# base-6u-generic-xau4.net
KiCad netlist of a schematic drawn in EAGLE
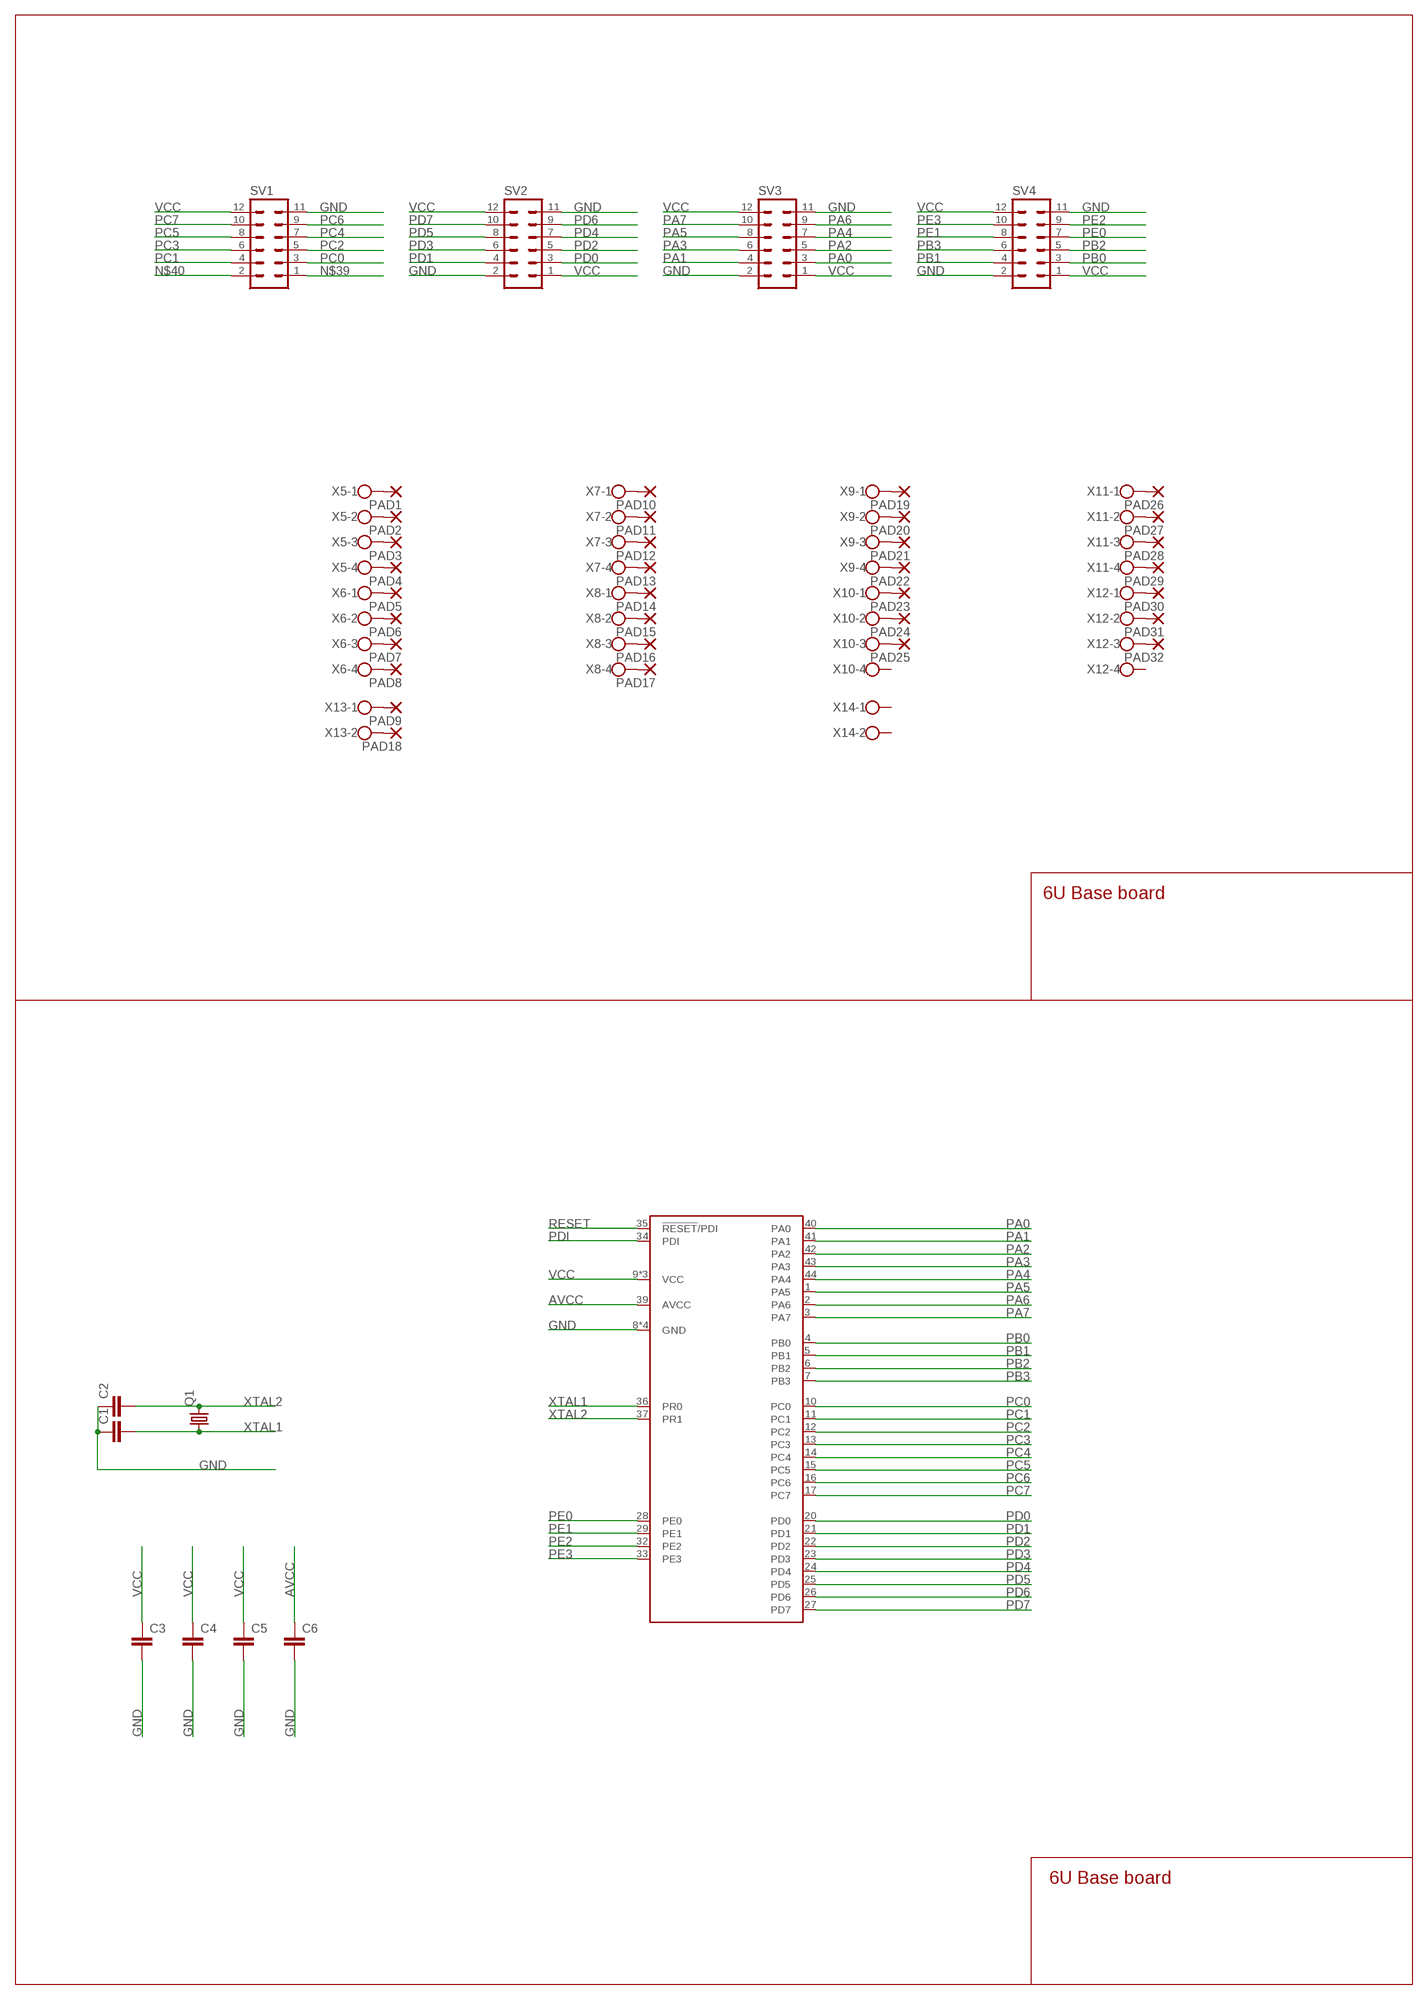
[diagram p0: schematic, sheet 1]

(export (version "E")
  (design (tool "Eeschema 10.0.6"))
  (components
    (comp (ref "C1")
      (value "C-EUC0805")
      (footprint "eagle-import:C0805")
      (libsource (lib "eagle-import") (part "C-EUC0805"))
    )
    (comp (ref "C2")
      (value "C-EUC0805")
      (footprint "eagle-import:C0805")
      (libsource (lib "eagle-import") (part "C-EUC0805"))
    )
    (comp (ref "C3")
      (value "C-EUC0603")
      (footprint "eagle-import:C0603")
      (libsource (lib "eagle-import") (part "C-EUC0603"))
    )
    (comp (ref "C4")
      (value "C-EUC0603")
      (footprint "eagle-import:C0603")
      (libsource (lib "eagle-import") (part "C-EUC0603"))
    )
    (comp (ref "C5")
      (value "C-EUC0603")
      (footprint "eagle-import:C0603")
      (libsource (lib "eagle-import") (part "C-EUC0603"))
    )
    (comp (ref "C6")
      (value "C-EUC0603")
      (footprint "eagle-import:C0603")
      (libsource (lib "eagle-import") (part "C-EUC0603"))
    )
    (comp (ref "PAD1")
      (value "2,54/0,8")
      (footprint "eagle-import:2,54_0,8")
      (libsource (lib "eagle-import") (part "2,54/0,8"))
    )
    (comp (ref "PAD2")
      (value "2,54/0,8")
      (footprint "eagle-import:2,54_0,8")
      (libsource (lib "eagle-import") (part "2,54/0,8"))
    )
    (comp (ref "PAD3")
      (value "2,54/0,8")
      (footprint "eagle-import:2,54_0,8")
      (libsource (lib "eagle-import") (part "2,54/0,8"))
    )
    (comp (ref "PAD4")
      (value "2,54/0,8")
      (footprint "eagle-import:2,54_0,8")
      (libsource (lib "eagle-import") (part "2,54/0,8"))
    )
    (comp (ref "PAD5")
      (value "2,54/0,8")
      (footprint "eagle-import:2,54_0,8")
      (libsource (lib "eagle-import") (part "2,54/0,8"))
    )
    (comp (ref "PAD6")
      (value "2,54/0,8")
      (footprint "eagle-import:2,54_0,8")
      (libsource (lib "eagle-import") (part "2,54/0,8"))
    )
    (comp (ref "PAD7")
      (value "2,54/0,8")
      (footprint "eagle-import:2,54_0,8")
      (libsource (lib "eagle-import") (part "2,54/0,8"))
    )
    (comp (ref "PAD8")
      (value "2,54/0,8")
      (footprint "eagle-import:2,54_0,8")
      (libsource (lib "eagle-import") (part "2,54/0,8"))
    )
    (comp (ref "PAD9")
      (value "2,54/0,8")
      (footprint "eagle-import:2,54_0,8")
      (libsource (lib "eagle-import") (part "2,54/0,8"))
    )
    (comp (ref "PAD10")
      (value "2,54/0,8")
      (footprint "eagle-import:2,54_0,8")
      (libsource (lib "eagle-import") (part "2,54/0,8"))
    )
    (comp (ref "PAD11")
      (value "2,54/0,8")
      (footprint "eagle-import:2,54_0,8")
      (libsource (lib "eagle-import") (part "2,54/0,8"))
    )
    (comp (ref "PAD12")
      (value "2,54/0,8")
      (footprint "eagle-import:2,54_0,8")
      (libsource (lib "eagle-import") (part "2,54/0,8"))
    )
    (comp (ref "PAD13")
      (value "2,54/0,8")
      (footprint "eagle-import:2,54_0,8")
      (libsource (lib "eagle-import") (part "2,54/0,8"))
    )
    (comp (ref "PAD14")
      (value "2,54/0,8")
      (footprint "eagle-import:2,54_0,8")
      (libsource (lib "eagle-import") (part "2,54/0,8"))
    )
    (comp (ref "PAD15")
      (value "2,54/0,8")
      (footprint "eagle-import:2,54_0,8")
      (libsource (lib "eagle-import") (part "2,54/0,8"))
    )
    (comp (ref "PAD16")
      (value "2,54/0,8")
      (footprint "eagle-import:2,54_0,8")
      (libsource (lib "eagle-import") (part "2,54/0,8"))
    )
    (comp (ref "PAD17")
      (value "2,54/0,8")
      (footprint "eagle-import:2,54_0,8")
      (libsource (lib "eagle-import") (part "2,54/0,8"))
    )
    (comp (ref "PAD18")
      (value "2,54/0,8")
      (footprint "eagle-import:2,54_0,8")
      (libsource (lib "eagle-import") (part "2,54/0,8"))
    )
    (comp (ref "PAD19")
      (value "2,54/0,8")
      (footprint "eagle-import:2,54_0,8")
      (libsource (lib "eagle-import") (part "2,54/0,8"))
    )
    (comp (ref "PAD20")
      (value "2,54/0,8")
      (footprint "eagle-import:2,54_0,8")
      (libsource (lib "eagle-import") (part "2,54/0,8"))
    )
    (comp (ref "PAD21")
      (value "2,54/0,8")
      (footprint "eagle-import:2,54_0,8")
      (libsource (lib "eagle-import") (part "2,54/0,8"))
    )
    (comp (ref "PAD22")
      (value "2,54/0,8")
      (footprint "eagle-import:2,54_0,8")
      (libsource (lib "eagle-import") (part "2,54/0,8"))
    )
    (comp (ref "PAD23")
      (value "2,54/0,8")
      (footprint "eagle-import:2,54_0,8")
      (libsource (lib "eagle-import") (part "2,54/0,8"))
    )
    (comp (ref "PAD24")
      (value "2,54/0,8")
      (footprint "eagle-import:2,54_0,8")
      (libsource (lib "eagle-import") (part "2,54/0,8"))
    )
    (comp (ref "PAD25")
      (value "2,54/0,8")
      (footprint "eagle-import:2,54_0,8")
      (libsource (lib "eagle-import") (part "2,54/0,8"))
    )
    (comp (ref "PAD26")
      (value "2,54/0,8")
      (footprint "eagle-import:2,54_0,8")
      (libsource (lib "eagle-import") (part "2,54/0,8"))
    )
    (comp (ref "PAD27")
      (value "2,54/0,8")
      (footprint "eagle-import:2,54_0,8")
      (libsource (lib "eagle-import") (part "2,54/0,8"))
    )
    (comp (ref "PAD28")
      (value "2,54/0,8")
      (footprint "eagle-import:2,54_0,8")
      (libsource (lib "eagle-import") (part "2,54/0,8"))
    )
    (comp (ref "PAD29")
      (value "2,54/0,8")
      (footprint "eagle-import:2,54_0,8")
      (libsource (lib "eagle-import") (part "2,54/0,8"))
    )
    (comp (ref "PAD30")
      (value "2,54/0,8")
      (footprint "eagle-import:2,54_0,8")
      (libsource (lib "eagle-import") (part "2,54/0,8"))
    )
    (comp (ref "PAD31")
      (value "2,54/0,8")
      (footprint "eagle-import:2,54_0,8")
      (libsource (lib "eagle-import") (part "2,54/0,8"))
    )
    (comp (ref "PAD32")
      (value "2,54/0,8")
      (footprint "eagle-import:2,54_0,8")
      (libsource (lib "eagle-import") (part "2,54/0,8"))
    )
    (comp (ref "Q1")
      (value "CRYSTALHC49S")
      (footprint "eagle-import:HC49_S")
      (libsource (lib "eagle-import") (part "CRYSTALHC49S"))
    )
    (comp (ref "SV1")
      (value "MA06-2")
      (footprint "eagle-import:MA06-2")
      (libsource (lib "eagle-import") (part "MA06-2"))
    )
    (comp (ref "SV2")
      (value "MA06-2")
      (footprint "eagle-import:MA06-2")
      (libsource (lib "eagle-import") (part "MA06-2"))
    )
    (comp (ref "SV3")
      (value "MA06-2")
      (footprint "eagle-import:MA06-2")
      (libsource (lib "eagle-import") (part "MA06-2"))
    )
    (comp (ref "SV4")
      (value "MA06-2")
      (footprint "eagle-import:MA06-2")
      (libsource (lib "eagle-import") (part "MA06-2"))
    )
    (comp (ref "U1")
      (value "ATXMEGA32A4U-AU")
      (footprint "eagle-import:TQFP-44A-44")
      (libsource (lib "eagle-import") (part "ATXMEGA32A4U-AU"))
    )
    (comp (ref "X5")
      (value "W237-4")
      (footprint "eagle-import:W237-4")
      (libsource (lib "eagle-import") (part "W237-4"))
    )
    (comp (ref "X6")
      (value "W237-4")
      (footprint "eagle-import:W237-4")
      (libsource (lib "eagle-import") (part "W237-4"))
    )
    (comp (ref "X7")
      (value "W237-4")
      (footprint "eagle-import:W237-4")
      (libsource (lib "eagle-import") (part "W237-4"))
    )
    (comp (ref "X8")
      (value "W237-4")
      (footprint "eagle-import:W237-4")
      (libsource (lib "eagle-import") (part "W237-4"))
    )
    (comp (ref "X9")
      (value "W237-4")
      (footprint "eagle-import:W237-4")
      (libsource (lib "eagle-import") (part "W237-4"))
    )
    (comp (ref "X10")
      (value "W237-4")
      (footprint "eagle-import:W237-4")
      (libsource (lib "eagle-import") (part "W237-4"))
    )
    (comp (ref "X11")
      (value "W237-4")
      (footprint "eagle-import:W237-4")
      (libsource (lib "eagle-import") (part "W237-4"))
    )
    (comp (ref "X12")
      (value "W237-4")
      (footprint "eagle-import:W237-4")
      (libsource (lib "eagle-import") (part "W237-4"))
    )
    (comp (ref "X13")
      (value "W237-102")
      (footprint "eagle-import:W237-102")
      (fields (field (name "MPN") "237-102"))
      (libsource (lib "eagle-import") (part "W237-102"))
    )
    (comp (ref "X14")
      (value "W237-102")
      (footprint "eagle-import:W237-102")
      (fields (field (name "MPN") "237-102"))
      (libsource (lib "eagle-import") (part "W237-102"))
    )
  )
  (nets
    (net (code "1") (name "/AVCC") (class "Default")
      (node (ref "C6") (pin "1") (pinfunction "1_1") (pintype "passive"))
      (node (ref "U1") (pin "39") (pinfunction "AVCC_39") (pintype "power_in"))
    )
    (net (code "2") (name "/GND") (class "Default")
      (node (ref "C1") (pin "1") (pinfunction "1_1") (pintype "passive"))
      (node (ref "C2") (pin "1") (pinfunction "1_1") (pintype "passive"))
      (node (ref "C3") (pin "2") (pinfunction "2_2") (pintype "passive"))
      (node (ref "C4") (pin "2") (pinfunction "2_2") (pintype "passive"))
      (node (ref "C5") (pin "2") (pinfunction "2_2") (pintype "passive"))
      (node (ref "C6") (pin "2") (pinfunction "2_2") (pintype "passive"))
      (node (ref "SV1") (pin "11") (pinfunction "11_11") (pintype "passive"))
      (node (ref "SV2") (pin "11") (pinfunction "11_11") (pintype "passive"))
      (node (ref "SV2") (pin "2") (pinfunction "2_2") (pintype "passive"))
      (node (ref "SV3") (pin "11") (pinfunction "11_11") (pintype "passive"))
      (node (ref "SV3") (pin "2") (pinfunction "2_2") (pintype "passive"))
      (node (ref "SV4") (pin "11") (pinfunction "11_11") (pintype "passive"))
      (node (ref "SV4") (pin "2") (pinfunction "2_2") (pintype "passive"))
      (node (ref "U1") (pin "18") (pinfunction "GND_18") (pintype "power_in"))
      (node (ref "U1") (pin "30") (pinfunction "GND_30") (pintype "power_in"))
      (node (ref "U1") (pin "38") (pinfunction "GND_38") (pintype "power_in"))
      (node (ref "U1") (pin "8") (pinfunction "GND_8") (pintype "power_in"))
    )
    (net (code "3") (name "/N$39") (class "Default")
      (node (ref "SV1") (pin "1") (pinfunction "1_1") (pintype "passive"))
    )
    (net (code "4") (name "/N$40") (class "Default")
      (node (ref "SV1") (pin "2") (pinfunction "2_2") (pintype "passive"))
    )
    (net (code "5") (name "/PA0") (class "Default")
      (node (ref "SV3") (pin "3") (pinfunction "3_3") (pintype "passive"))
      (node (ref "U1") (pin "40") (pinfunction "PA0_40") (pintype "bidirectional"))
    )
    (net (code "6") (name "/PA1") (class "Default")
      (node (ref "SV3") (pin "4") (pinfunction "4_4") (pintype "passive"))
      (node (ref "U1") (pin "41") (pinfunction "PA1_41") (pintype "bidirectional"))
    )
    (net (code "7") (name "/PA2") (class "Default")
      (node (ref "SV3") (pin "5") (pinfunction "5_5") (pintype "passive"))
      (node (ref "U1") (pin "42") (pinfunction "PA2_42") (pintype "bidirectional"))
    )
    (net (code "8") (name "/PA3") (class "Default")
      (node (ref "SV3") (pin "6") (pinfunction "6_6") (pintype "passive"))
      (node (ref "U1") (pin "43") (pinfunction "PA3_43") (pintype "bidirectional"))
    )
    (net (code "9") (name "/PA4") (class "Default")
      (node (ref "SV3") (pin "7") (pinfunction "7_7") (pintype "passive"))
      (node (ref "U1") (pin "44") (pinfunction "PA4_44") (pintype "bidirectional"))
    )
    (net (code "10") (name "/PA5") (class "Default")
      (node (ref "SV3") (pin "8") (pinfunction "8_8") (pintype "passive"))
      (node (ref "U1") (pin "1") (pinfunction "PA5_1") (pintype "bidirectional"))
    )
    (net (code "11") (name "/PA6") (class "Default")
      (node (ref "SV3") (pin "9") (pinfunction "9_9") (pintype "passive"))
      (node (ref "U1") (pin "2") (pinfunction "PA6_2") (pintype "bidirectional"))
    )
    (net (code "12") (name "/PA7") (class "Default")
      (node (ref "SV3") (pin "10") (pinfunction "10_10") (pintype "passive"))
      (node (ref "U1") (pin "3") (pinfunction "PA7_3") (pintype "bidirectional"))
    )
    (net (code "13") (name "/PB0") (class "Default")
      (node (ref "SV4") (pin "3") (pinfunction "3_3") (pintype "passive"))
      (node (ref "U1") (pin "4") (pinfunction "PB0_4") (pintype "bidirectional"))
    )
    (net (code "14") (name "/PB1") (class "Default")
      (node (ref "SV4") (pin "4") (pinfunction "4_4") (pintype "passive"))
      (node (ref "U1") (pin "5") (pinfunction "PB1_5") (pintype "bidirectional"))
    )
    (net (code "15") (name "/PB2") (class "Default")
      (node (ref "SV4") (pin "5") (pinfunction "5_5") (pintype "passive"))
      (node (ref "U1") (pin "6") (pinfunction "PB2_6") (pintype "bidirectional"))
    )
    (net (code "16") (name "/PB3") (class "Default")
      (node (ref "SV4") (pin "6") (pinfunction "6_6") (pintype "passive"))
      (node (ref "U1") (pin "7") (pinfunction "PB3_7") (pintype "bidirectional"))
    )
    (net (code "17") (name "/PC0") (class "Default")
      (node (ref "SV1") (pin "3") (pinfunction "3_3") (pintype "passive"))
      (node (ref "U1") (pin "10") (pinfunction "PC0_10") (pintype "bidirectional"))
    )
    (net (code "18") (name "/PC1") (class "Default")
      (node (ref "SV1") (pin "4") (pinfunction "4_4") (pintype "passive"))
      (node (ref "U1") (pin "11") (pinfunction "PC1_11") (pintype "bidirectional"))
    )
    (net (code "19") (name "/PC2") (class "Default")
      (node (ref "SV1") (pin "5") (pinfunction "5_5") (pintype "passive"))
      (node (ref "U1") (pin "12") (pinfunction "PC2_12") (pintype "bidirectional"))
    )
    (net (code "20") (name "/PC3") (class "Default")
      (node (ref "SV1") (pin "6") (pinfunction "6_6") (pintype "passive"))
      (node (ref "U1") (pin "13") (pinfunction "PC3_13") (pintype "bidirectional"))
    )
    (net (code "21") (name "/PC4") (class "Default")
      (node (ref "SV1") (pin "7") (pinfunction "7_7") (pintype "passive"))
      (node (ref "U1") (pin "14") (pinfunction "PC4_14") (pintype "bidirectional"))
    )
    (net (code "22") (name "/PC5") (class "Default")
      (node (ref "SV1") (pin "8") (pinfunction "8_8") (pintype "passive"))
      (node (ref "U1") (pin "15") (pinfunction "PC5_15") (pintype "bidirectional"))
    )
    (net (code "23") (name "/PC6") (class "Default")
      (node (ref "SV1") (pin "9") (pinfunction "9_9") (pintype "passive"))
      (node (ref "U1") (pin "16") (pinfunction "PC6_16") (pintype "bidirectional"))
    )
    (net (code "24") (name "/PC7") (class "Default")
      (node (ref "SV1") (pin "10") (pinfunction "10_10") (pintype "passive"))
      (node (ref "U1") (pin "17") (pinfunction "PC7_17") (pintype "bidirectional"))
    )
    (net (code "25") (name "/PD0") (class "Default")
      (node (ref "SV2") (pin "3") (pinfunction "3_3") (pintype "passive"))
      (node (ref "U1") (pin "20") (pinfunction "PD0_20") (pintype "bidirectional"))
    )
    (net (code "26") (name "/PD1") (class "Default")
      (node (ref "SV2") (pin "4") (pinfunction "4_4") (pintype "passive"))
      (node (ref "U1") (pin "21") (pinfunction "PD1_21") (pintype "bidirectional"))
    )
    (net (code "27") (name "/PD2") (class "Default")
      (node (ref "SV2") (pin "5") (pinfunction "5_5") (pintype "passive"))
      (node (ref "U1") (pin "22") (pinfunction "PD2_22") (pintype "bidirectional"))
    )
    (net (code "28") (name "/PD3") (class "Default")
      (node (ref "SV2") (pin "6") (pinfunction "6_6") (pintype "passive"))
      (node (ref "U1") (pin "23") (pinfunction "PD3_23") (pintype "bidirectional"))
    )
    (net (code "29") (name "/PD4") (class "Default")
      (node (ref "SV2") (pin "7") (pinfunction "7_7") (pintype "passive"))
      (node (ref "U1") (pin "24") (pinfunction "PD4_24") (pintype "bidirectional"))
    )
    (net (code "30") (name "/PD5") (class "Default")
      (node (ref "SV2") (pin "8") (pinfunction "8_8") (pintype "passive"))
      (node (ref "U1") (pin "25") (pinfunction "PD5_25") (pintype "bidirectional"))
    )
    (net (code "31") (name "/PD6") (class "Default")
      (node (ref "SV2") (pin "9") (pinfunction "9_9") (pintype "passive"))
      (node (ref "U1") (pin "26") (pinfunction "PD6_26") (pintype "bidirectional"))
    )
    (net (code "32") (name "/PD7") (class "Default")
      (node (ref "SV2") (pin "10") (pinfunction "10_10") (pintype "passive"))
      (node (ref "U1") (pin "27") (pinfunction "PD7_27") (pintype "bidirectional"))
    )
    (net (code "33") (name "/PDI") (class "Default")
      (node (ref "U1") (pin "34") (pinfunction "PDI_34") (pintype "bidirectional"))
    )
    (net (code "34") (name "/PE0") (class "Default")
      (node (ref "SV4") (pin "7") (pinfunction "7_7") (pintype "passive"))
      (node (ref "U1") (pin "28") (pinfunction "PE0_28") (pintype "bidirectional"))
    )
    (net (code "35") (name "/PE1") (class "Default")
      (node (ref "SV4") (pin "8") (pinfunction "8_8") (pintype "passive"))
      (node (ref "U1") (pin "29") (pinfunction "PE1_29") (pintype "bidirectional"))
    )
    (net (code "36") (name "/PE2") (class "Default")
      (node (ref "SV4") (pin "9") (pinfunction "9_9") (pintype "passive"))
      (node (ref "U1") (pin "32") (pinfunction "PE2_32") (pintype "bidirectional"))
    )
    (net (code "37") (name "/PE3") (class "Default")
      (node (ref "SV4") (pin "10") (pinfunction "10_10") (pintype "passive"))
      (node (ref "U1") (pin "33") (pinfunction "PE3_33") (pintype "bidirectional"))
    )
    (net (code "38") (name "/RESET") (class "Default")
      (node (ref "U1") (pin "35") (pinfunction "~{RESET}/PDI_35") (pintype "bidirectional"))
    )
    (net (code "39") (name "/VCC") (class "Default")
      (node (ref "C3") (pin "1") (pinfunction "1_1") (pintype "passive"))
      (node (ref "C4") (pin "1") (pinfunction "1_1") (pintype "passive"))
      (node (ref "C5") (pin "1") (pinfunction "1_1") (pintype "passive"))
      (node (ref "SV1") (pin "12") (pinfunction "12_12") (pintype "passive"))
      (node (ref "SV2") (pin "1") (pinfunction "1_1") (pintype "passive"))
      (node (ref "SV2") (pin "12") (pinfunction "12_12") (pintype "passive"))
      (node (ref "SV3") (pin "1") (pinfunction "1_1") (pintype "passive"))
      (node (ref "SV3") (pin "12") (pinfunction "12_12") (pintype "passive"))
      (node (ref "SV4") (pin "1") (pinfunction "1_1") (pintype "passive"))
      (node (ref "SV4") (pin "12") (pinfunction "12_12") (pintype "passive"))
      (node (ref "U1") (pin "19") (pinfunction "VCC_19") (pintype "power_in"))
      (node (ref "U1") (pin "31") (pinfunction "VCC_31") (pintype "power_in"))
      (node (ref "U1") (pin "9") (pinfunction "VCC_9") (pintype "power_in"))
    )
    (net (code "40") (name "/XTAL1") (class "Default")
      (node (ref "C1") (pin "2") (pinfunction "2_2") (pintype "passive"))
      (node (ref "Q1") (pin "1") (pinfunction "1_1") (pintype "passive"))
      (node (ref "U1") (pin "36") (pinfunction "PR0_36") (pintype "bidirectional"))
    )
    (net (code "41") (name "/XTAL2") (class "Default")
      (node (ref "C2") (pin "2") (pinfunction "2_2") (pintype "passive"))
      (node (ref "Q1") (pin "2") (pinfunction "2_2") (pintype "passive"))
      (node (ref "U1") (pin "37") (pinfunction "PR1_37") (pintype "bidirectional"))
    )
    (net (code "42") (name "Net-(PAD1-P)") (class "Default")
      (node (ref "PAD1") (pin "1") (pinfunction "P_1") (pintype "passive"))
      (node (ref "X5") (pin "1") (pinfunction "KL_1") (pintype "passive"))
    )
    (net (code "43") (name "Net-(PAD2-P)") (class "Default")
      (node (ref "PAD2") (pin "1") (pinfunction "P_1") (pintype "passive"))
      (node (ref "X5") (pin "2") (pinfunction "KL_2") (pintype "passive"))
    )
    (net (code "44") (name "Net-(PAD3-P)") (class "Default")
      (node (ref "PAD3") (pin "1") (pinfunction "P_1") (pintype "passive"))
      (node (ref "X5") (pin "3") (pinfunction "KL_3") (pintype "passive"))
    )
    (net (code "45") (name "Net-(PAD4-P)") (class "Default")
      (node (ref "PAD4") (pin "1") (pinfunction "P_1") (pintype "passive"))
      (node (ref "X5") (pin "4") (pinfunction "KL_4") (pintype "passive"))
    )
    (net (code "46") (name "Net-(PAD5-P)") (class "Default")
      (node (ref "PAD5") (pin "1") (pinfunction "P_1") (pintype "passive"))
      (node (ref "X6") (pin "1") (pinfunction "KL_1") (pintype "passive"))
    )
    (net (code "47") (name "Net-(PAD6-P)") (class "Default")
      (node (ref "PAD6") (pin "1") (pinfunction "P_1") (pintype "passive"))
      (node (ref "X6") (pin "2") (pinfunction "KL_2") (pintype "passive"))
    )
    (net (code "48") (name "Net-(PAD7-P)") (class "Default")
      (node (ref "PAD7") (pin "1") (pinfunction "P_1") (pintype "passive"))
      (node (ref "X6") (pin "3") (pinfunction "KL_3") (pintype "passive"))
    )
    (net (code "49") (name "Net-(PAD8-P)") (class "Default")
      (node (ref "PAD8") (pin "1") (pinfunction "P_1") (pintype "passive"))
      (node (ref "X6") (pin "4") (pinfunction "KL_4") (pintype "passive"))
    )
    (net (code "50") (name "Net-(PAD9-P)") (class "Default")
      (node (ref "PAD9") (pin "1") (pinfunction "P_1") (pintype "passive"))
      (node (ref "X13") (pin "1") (pinfunction "KL_1") (pintype "passive"))
    )
    (net (code "51") (name "Net-(PAD10-P)") (class "Default")
      (node (ref "PAD10") (pin "1") (pinfunction "P_1") (pintype "passive"))
      (node (ref "X7") (pin "1") (pinfunction "KL_1") (pintype "passive"))
    )
    (net (code "52") (name "Net-(PAD11-P)") (class "Default")
      (node (ref "PAD11") (pin "1") (pinfunction "P_1") (pintype "passive"))
      (node (ref "X7") (pin "2") (pinfunction "KL_2") (pintype "passive"))
    )
    (net (code "53") (name "Net-(PAD12-P)") (class "Default")
      (node (ref "PAD12") (pin "1") (pinfunction "P_1") (pintype "passive"))
      (node (ref "X7") (pin "3") (pinfunction "KL_3") (pintype "passive"))
    )
    (net (code "54") (name "Net-(PAD13-P)") (class "Default")
      (node (ref "PAD13") (pin "1") (pinfunction "P_1") (pintype "passive"))
      (node (ref "X7") (pin "4") (pinfunction "KL_4") (pintype "passive"))
    )
    (net (code "55") (name "Net-(PAD14-P)") (class "Default")
      (node (ref "PAD14") (pin "1") (pinfunction "P_1") (pintype "passive"))
      (node (ref "X8") (pin "1") (pinfunction "KL_1") (pintype "passive"))
    )
    (net (code "56") (name "Net-(PAD15-P)") (class "Default")
      (node (ref "PAD15") (pin "1") (pinfunction "P_1") (pintype "passive"))
      (node (ref "X8") (pin "2") (pinfunction "KL_2") (pintype "passive"))
    )
    (net (code "57") (name "Net-(PAD16-P)") (class "Default")
      (node (ref "PAD16") (pin "1") (pinfunction "P_1") (pintype "passive"))
      (node (ref "X8") (pin "3") (pinfunction "KL_3") (pintype "passive"))
    )
    (net (code "58") (name "Net-(PAD17-P)") (class "Default")
      (node (ref "PAD17") (pin "1") (pinfunction "P_1") (pintype "passive"))
      (node (ref "X8") (pin "4") (pinfunction "KL_4") (pintype "passive"))
    )
    (net (code "59") (name "Net-(PAD18-P)") (class "Default")
      (node (ref "PAD18") (pin "1") (pinfunction "P_1") (pintype "passive"))
      (node (ref "X13") (pin "2") (pinfunction "KL_2") (pintype "passive"))
    )
    (net (code "60") (name "Net-(PAD19-P)") (class "Default")
      (node (ref "PAD19") (pin "1") (pinfunction "P_1") (pintype "passive"))
      (node (ref "X9") (pin "1") (pinfunction "KL_1") (pintype "passive"))
    )
    (net (code "61") (name "Net-(PAD20-P)") (class "Default")
      (node (ref "PAD20") (pin "1") (pinfunction "P_1") (pintype "passive"))
      (node (ref "X9") (pin "2") (pinfunction "KL_2") (pintype "passive"))
    )
    (net (code "62") (name "Net-(PAD21-P)") (class "Default")
      (node (ref "PAD21") (pin "1") (pinfunction "P_1") (pintype "passive"))
      (node (ref "X9") (pin "3") (pinfunction "KL_3") (pintype "passive"))
    )
    (net (code "63") (name "Net-(PAD22-P)") (class "Default")
      (node (ref "PAD22") (pin "1") (pinfunction "P_1") (pintype "passive"))
      (node (ref "X9") (pin "4") (pinfunction "KL_4") (pintype "passive"))
    )
    (net (code "64") (name "Net-(PAD23-P)") (class "Default")
      (node (ref "PAD23") (pin "1") (pinfunction "P_1") (pintype "passive"))
      (node (ref "X10") (pin "1") (pinfunction "KL_1") (pintype "passive"))
    )
    (net (code "65") (name "Net-(PAD24-P)") (class "Default")
      (node (ref "PAD24") (pin "1") (pinfunction "P_1") (pintype "passive"))
      (node (ref "X10") (pin "2") (pinfunction "KL_2") (pintype "passive"))
    )
    (net (code "66") (name "Net-(PAD25-P)") (class "Default")
      (node (ref "PAD25") (pin "1") (pinfunction "P_1") (pintype "passive"))
      (node (ref "X10") (pin "3") (pinfunction "KL_3") (pintype "passive"))
    )
    (net (code "67") (name "Net-(PAD26-P)") (class "Default")
      (node (ref "PAD26") (pin "1") (pinfunction "P_1") (pintype "passive"))
      (node (ref "X11") (pin "1") (pinfunction "KL_1") (pintype "passive"))
    )
    (net (code "68") (name "Net-(PAD27-P)") (class "Default")
      (node (ref "PAD27") (pin "1") (pinfunction "P_1") (pintype "passive"))
      (node (ref "X11") (pin "2") (pinfunction "KL_2") (pintype "passive"))
    )
    (net (code "69") (name "Net-(PAD28-P)") (class "Default")
      (node (ref "PAD28") (pin "1") (pinfunction "P_1") (pintype "passive"))
      (node (ref "X11") (pin "3") (pinfunction "KL_3") (pintype "passive"))
    )
    (net (code "70") (name "Net-(PAD29-P)") (class "Default")
      (node (ref "PAD29") (pin "1") (pinfunction "P_1") (pintype "passive"))
      (node (ref "X11") (pin "4") (pinfunction "KL_4") (pintype "passive"))
    )
    (net (code "71") (name "Net-(PAD30-P)") (class "Default")
      (node (ref "PAD30") (pin "1") (pinfunction "P_1") (pintype "passive"))
      (node (ref "X12") (pin "1") (pinfunction "KL_1") (pintype "passive"))
    )
    (net (code "72") (name "Net-(PAD31-P)") (class "Default")
      (node (ref "PAD31") (pin "1") (pinfunction "P_1") (pintype "passive"))
      (node (ref "X12") (pin "2") (pinfunction "KL_2") (pintype "passive"))
    )
    (net (code "73") (name "Net-(PAD32-P)") (class "Default")
      (node (ref "PAD32") (pin "1") (pinfunction "P_1") (pintype "passive"))
      (node (ref "X12") (pin "3") (pinfunction "KL_3") (pintype "passive"))
    )
    (net (code "74") (name "unconnected-(X10D-KL-Pad4)") (class "Default")
      (node (ref "X10") (pin "4") (pinfunction "KL_4") (pintype "passive"))
    )
    (net (code "75") (name "unconnected-(X12D-KL-Pad4)") (class "Default")
      (node (ref "X12") (pin "4") (pinfunction "KL_4") (pintype "passive"))
    )
    (net (code "76") (name "unconnected-(X14A-KL-Pad1)") (class "Default")
      (node (ref "X14") (pin "1") (pinfunction "KL_1") (pintype "passive"))
    )
    (net (code "77") (name "unconnected-(X14B-KL-Pad2)") (class "Default")
      (node (ref "X14") (pin "2") (pinfunction "KL_2") (pintype "passive"))
    )
  )
)
